# RN-131G_Breakout-v13.net
KiCad netlist of a schematic drawn in EAGLE
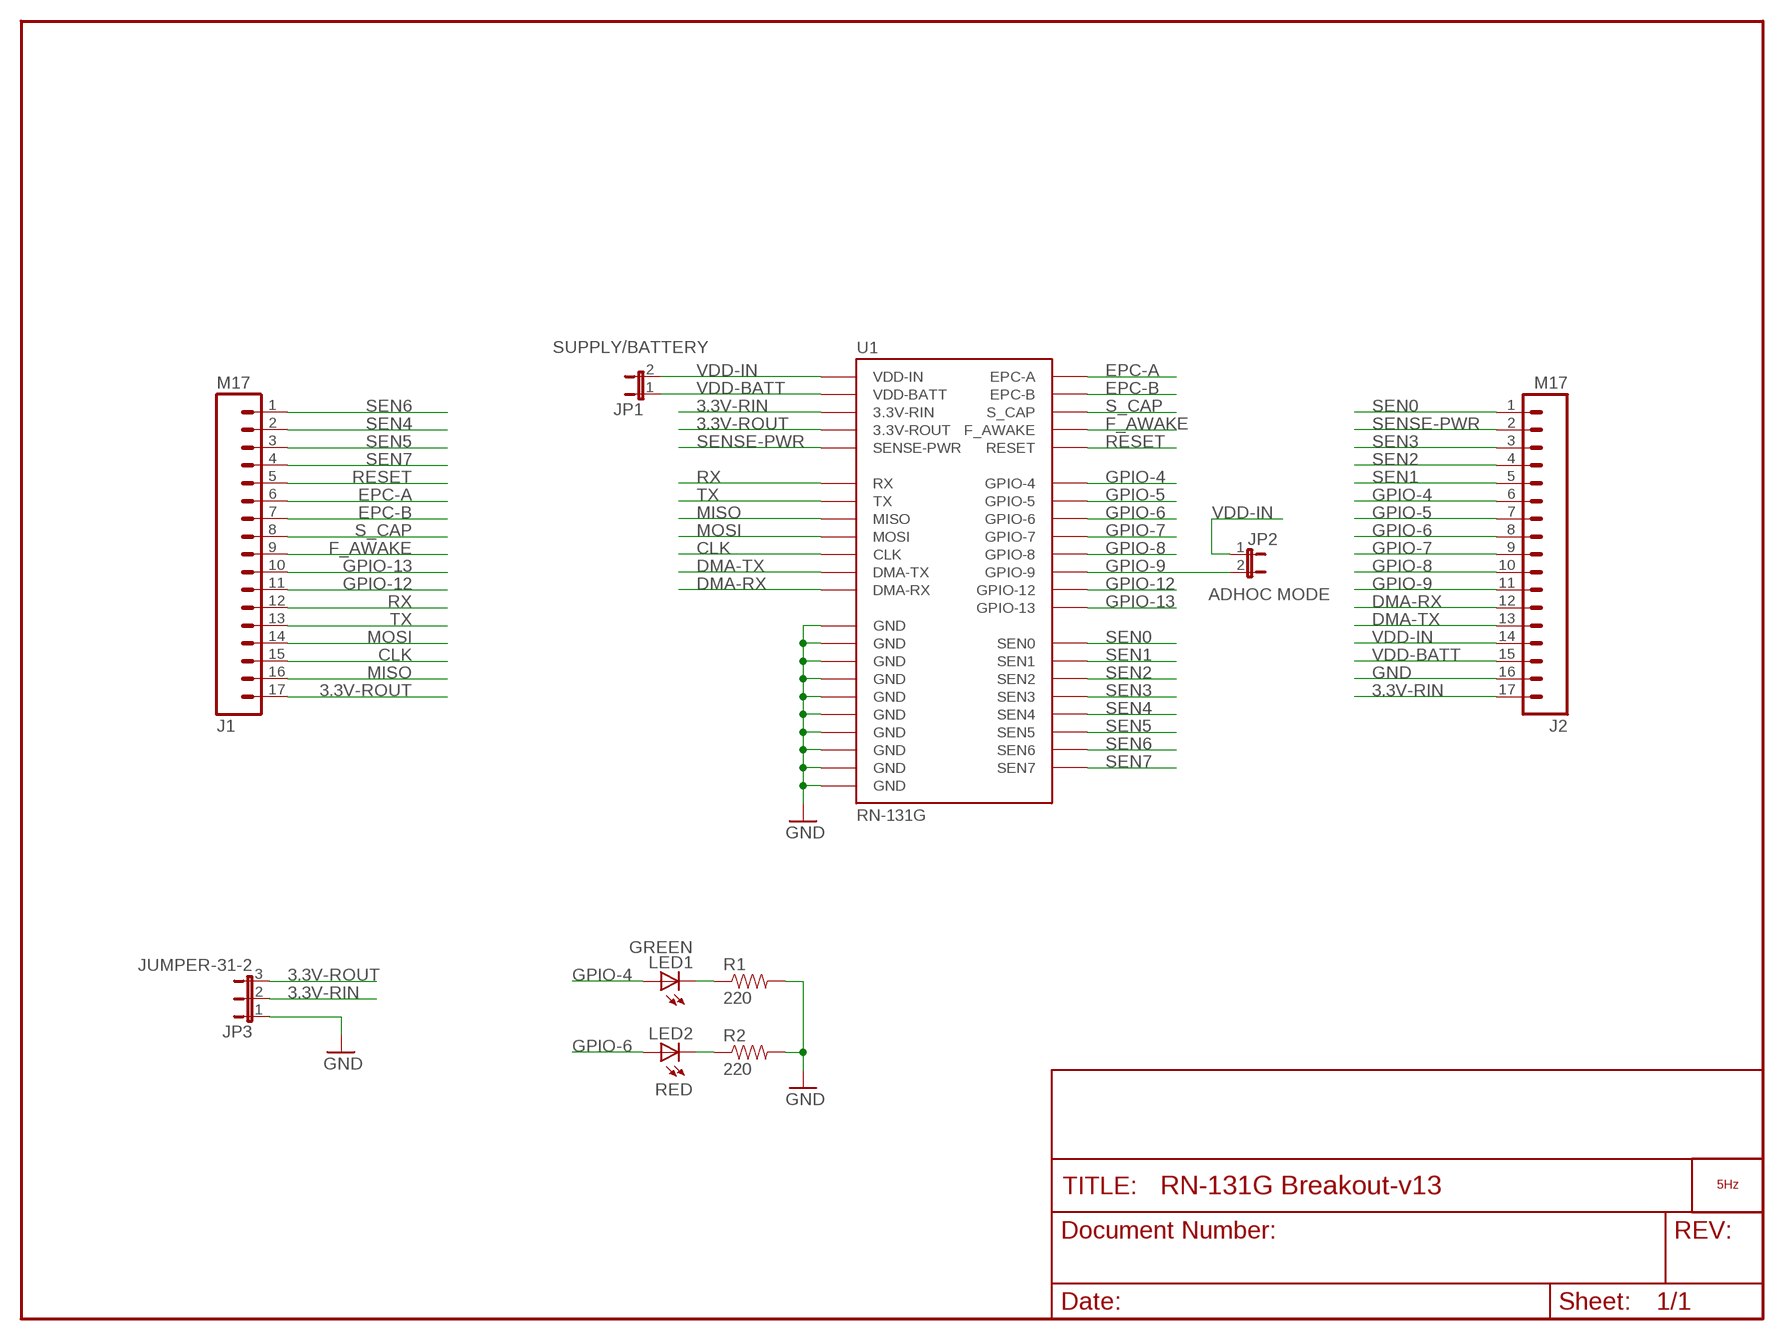
[diagram p0: schematic, sheet 1]

(export (version "E")
  (design (tool "Eeschema 10.0.6"))
  (components
    (comp (ref "J1")
      (value "M17")
      (footprint "eagle-import:1X17")
      (libsource (lib "eagle-import") (part "M17"))
    )
    (comp (ref "J2")
      (value "M17")
      (footprint "eagle-import:1X17")
      (libsource (lib "eagle-import") (part "M17"))
    )
    (comp (ref "JP1")
      (value "JUMPER-2SMD-NO")
      (footprint "eagle-import:SJ_2S-NO")
      (libsource (lib "eagle-import") (part "JUMPER-2SMD-NO"))
    )
    (comp (ref "JP2")
      (value "JUMPER-2SMD-NO")
      (footprint "eagle-import:SJ_2S-NO")
      (libsource (lib "eagle-import") (part "JUMPER-2SMD-NO"))
    )
    (comp (ref "JP3")
      (value "JUMPER-31-2")
      (footprint "eagle-import:SJ_3_PASTE1&2")
      (libsource (lib "eagle-import") (part "JUMPER-31-2"))
    )
    (comp (ref "LED1")
      (value "GREEN")
      (footprint "eagle-import:LED-0603")
      (libsource (lib "eagle-import") (part "LED0603"))
    )
    (comp (ref "LED2")
      (value "RED")
      (footprint "eagle-import:LED-0603")
      (libsource (lib "eagle-import") (part "LED0603"))
    )
    (comp (ref "LOGO1")
      (value "LOGO_5HZ_H_10MM")
      (footprint "eagle-import:5HZ_LOGO_H_10MM")
      (libsource (lib "eagle-import") (part "LOGO_5HZ_H_10MM"))
    )
    (comp (ref "R1")
      (value "220")
      (footprint "eagle-import:0402-RES")
      (libsource (lib "eagle-import") (part "RESISTOR0402-RES"))
    )
    (comp (ref "R2")
      (value "220")
      (footprint "eagle-import:0402-RES")
      (libsource (lib "eagle-import") (part "RESISTOR0402-RES"))
    )
    (comp (ref "U1")
      (value "RN-131G")
      (footprint "eagle-import:RN-131G")
      (libsource (lib "eagle-import") (part "RN-131G"))
    )
  )
  (nets
    (net (code "1") (name "/3.3V-RIN") (class "Default")
      (node (ref "J2") (pin "17") (pinfunction "17_17") (pintype "passive"))
      (node (ref "JP3") (pin "2") (pinfunction "2_2") (pintype "passive"))
      (node (ref "U1") (pin "P$18") (pinfunction "3.3V-RIN_P$18") (pintype "bidirectional"))
    )
    (net (code "2") (name "/3.3V-ROUT") (class "Default")
      (node (ref "J1") (pin "17") (pinfunction "17_17") (pintype "passive"))
      (node (ref "JP3") (pin "3") (pinfunction "3_3") (pintype "passive"))
      (node (ref "U1") (pin "P$17") (pinfunction "3.3V-ROUT_P$17") (pintype "bidirectional"))
    )
    (net (code "3") (name "/CLK") (class "Default")
      (node (ref "J1") (pin "15") (pinfunction "15_15") (pintype "passive"))
      (node (ref "U1") (pin "P$15") (pinfunction "CLK_P$15") (pintype "bidirectional"))
    )
    (net (code "4") (name "/DMA-RX") (class "Default")
      (node (ref "J2") (pin "12") (pinfunction "12_12") (pintype "passive"))
      (node (ref "U1") (pin "P$23") (pinfunction "DMA-RX_P$23") (pintype "bidirectional"))
    )
    (net (code "5") (name "/DMA-TX") (class "Default")
      (node (ref "J2") (pin "13") (pinfunction "13_13") (pintype "passive"))
      (node (ref "U1") (pin "P$22") (pinfunction "DMA-TX_P$22") (pintype "bidirectional"))
    )
    (net (code "6") (name "/EPC-A") (class "Default")
      (node (ref "J1") (pin "6") (pinfunction "6_6") (pintype "passive"))
      (node (ref "U1") (pin "P$6") (pinfunction "EPC-A_P$6") (pintype "bidirectional"))
    )
    (net (code "7") (name "/EPC-B") (class "Default")
      (node (ref "J1") (pin "7") (pinfunction "7_7") (pintype "passive"))
      (node (ref "U1") (pin "P$7") (pinfunction "EPC-B_P$7") (pintype "bidirectional"))
    )
    (net (code "8") (name "/F_AWAKE") (class "Default")
      (node (ref "J1") (pin "9") (pinfunction "9_9") (pintype "passive"))
      (node (ref "U1") (pin "P$9") (pinfunction "F_AWAKE_P$9") (pintype "bidirectional"))
    )
    (net (code "9") (name "/GPIO-4") (class "Default")
      (node (ref "J2") (pin "6") (pinfunction "6_6") (pintype "passive"))
      (node (ref "LED1") (pin "A") (pinfunction "A_A") (pintype "passive"))
      (node (ref "U1") (pin "P$29") (pinfunction "GPIO-4_P$29") (pintype "bidirectional"))
    )
    (net (code "10") (name "/GPIO-5") (class "Default")
      (node (ref "J2") (pin "7") (pinfunction "7_7") (pintype "passive"))
      (node (ref "U1") (pin "P$28") (pinfunction "GPIO-5_P$28") (pintype "bidirectional"))
    )
    (net (code "11") (name "/GPIO-6") (class "Default")
      (node (ref "J2") (pin "8") (pinfunction "8_8") (pintype "passive"))
      (node (ref "LED2") (pin "A") (pinfunction "A_A") (pintype "passive"))
      (node (ref "U1") (pin "P$27") (pinfunction "GPIO-6_P$27") (pintype "bidirectional"))
    )
    (net (code "12") (name "/GPIO-7") (class "Default")
      (node (ref "J2") (pin "9") (pinfunction "9_9") (pintype "passive"))
      (node (ref "U1") (pin "P$26") (pinfunction "GPIO-7_P$26") (pintype "bidirectional"))
    )
    (net (code "13") (name "/GPIO-8") (class "Default")
      (node (ref "J2") (pin "10") (pinfunction "10_10") (pintype "passive"))
      (node (ref "U1") (pin "P$25") (pinfunction "GPIO-8_P$25") (pintype "bidirectional"))
    )
    (net (code "14") (name "/GPIO-9") (class "Default")
      (node (ref "J2") (pin "11") (pinfunction "11_11") (pintype "passive"))
      (node (ref "JP2") (pin "2") (pinfunction "2_2") (pintype "passive"))
      (node (ref "U1") (pin "P$24") (pinfunction "GPIO-9_P$24") (pintype "bidirectional"))
    )
    (net (code "15") (name "/GPIO-12") (class "Default")
      (node (ref "J1") (pin "11") (pinfunction "11_11") (pintype "passive"))
      (node (ref "U1") (pin "P$11") (pinfunction "GPIO-12_P$11") (pintype "bidirectional"))
    )
    (net (code "16") (name "/GPIO-13") (class "Default")
      (node (ref "J1") (pin "10") (pinfunction "10_10") (pintype "passive"))
      (node (ref "U1") (pin "P$10") (pinfunction "GPIO-13_P$10") (pintype "bidirectional"))
    )
    (net (code "17") (name "/MISO") (class "Default")
      (node (ref "J1") (pin "16") (pinfunction "16_16") (pintype "passive"))
      (node (ref "U1") (pin "P$16") (pinfunction "MISO_P$16") (pintype "bidirectional"))
    )
    (net (code "18") (name "/MOSI") (class "Default")
      (node (ref "J1") (pin "14") (pinfunction "14_14") (pintype "passive"))
      (node (ref "U1") (pin "P$14") (pinfunction "MOSI_P$14") (pintype "bidirectional"))
    )
    (net (code "19") (name "/RESET") (class "Default")
      (node (ref "J1") (pin "5") (pinfunction "5_5") (pintype "passive"))
      (node (ref "U1") (pin "P$5") (pinfunction "RESET_P$5") (pintype "bidirectional"))
    )
    (net (code "20") (name "/RX") (class "Default")
      (node (ref "J1") (pin "12") (pinfunction "12_12") (pintype "passive"))
      (node (ref "U1") (pin "P$12") (pinfunction "RX_P$12") (pintype "bidirectional"))
    )
    (net (code "21") (name "/SEN0") (class "Default")
      (node (ref "J2") (pin "1") (pinfunction "1_1") (pintype "passive"))
      (node (ref "U1") (pin "P$34") (pinfunction "SEN0_P$34") (pintype "bidirectional"))
    )
    (net (code "22") (name "/SEN1") (class "Default")
      (node (ref "J2") (pin "5") (pinfunction "5_5") (pintype "passive"))
      (node (ref "U1") (pin "P$30") (pinfunction "SEN1_P$30") (pintype "bidirectional"))
    )
    (net (code "23") (name "/SEN2") (class "Default")
      (node (ref "J2") (pin "4") (pinfunction "4_4") (pintype "passive"))
      (node (ref "U1") (pin "P$31") (pinfunction "SEN2_P$31") (pintype "bidirectional"))
    )
    (net (code "24") (name "/SEN3") (class "Default")
      (node (ref "J2") (pin "3") (pinfunction "3_3") (pintype "passive"))
      (node (ref "U1") (pin "P$32") (pinfunction "SEN3_P$32") (pintype "bidirectional"))
    )
    (net (code "25") (name "/SEN4") (class "Default")
      (node (ref "J1") (pin "2") (pinfunction "2_2") (pintype "passive"))
      (node (ref "U1") (pin "P$2") (pinfunction "SEN4_P$2") (pintype "bidirectional"))
    )
    (net (code "26") (name "/SEN5") (class "Default")
      (node (ref "J1") (pin "3") (pinfunction "3_3") (pintype "passive"))
      (node (ref "U1") (pin "P$3") (pinfunction "SEN5_P$3") (pintype "bidirectional"))
    )
    (net (code "27") (name "/SEN6") (class "Default")
      (node (ref "J1") (pin "1") (pinfunction "1_1") (pintype "passive"))
      (node (ref "U1") (pin "P$1") (pinfunction "SEN6_P$1") (pintype "bidirectional"))
    )
    (net (code "28") (name "/SEN7") (class "Default")
      (node (ref "J1") (pin "4") (pinfunction "4_4") (pintype "passive"))
      (node (ref "U1") (pin "P$4") (pinfunction "SEN7_P$4") (pintype "bidirectional"))
    )
    (net (code "29") (name "/SENSE-PWR") (class "Default")
      (node (ref "J2") (pin "2") (pinfunction "2_2") (pintype "passive"))
      (node (ref "U1") (pin "P$33") (pinfunction "SENSE-PWR_P$33") (pintype "bidirectional"))
    )
    (net (code "30") (name "/S_CAP") (class "Default")
      (node (ref "J1") (pin "8") (pinfunction "8_8") (pintype "passive"))
      (node (ref "U1") (pin "P$8") (pinfunction "S_CAP_P$8") (pintype "bidirectional"))
    )
    (net (code "31") (name "/TX") (class "Default")
      (node (ref "J1") (pin "13") (pinfunction "13_13") (pintype "passive"))
      (node (ref "U1") (pin "P$13") (pinfunction "TX_P$13") (pintype "bidirectional"))
    )
    (net (code "32") (name "/VDD-BATT") (class "Default")
      (node (ref "J2") (pin "15") (pinfunction "15_15") (pintype "passive"))
      (node (ref "JP1") (pin "1") (pinfunction "1_1") (pintype "passive"))
      (node (ref "U1") (pin "P$20") (pinfunction "VDD-BATT_P$20") (pintype "bidirectional"))
    )
    (net (code "33") (name "/VDD-IN") (class "Default")
      (node (ref "J2") (pin "14") (pinfunction "14_14") (pintype "passive"))
      (node (ref "JP1") (pin "2") (pinfunction "2_2") (pintype "passive"))
      (node (ref "JP2") (pin "1") (pinfunction "1_1") (pintype "passive"))
      (node (ref "U1") (pin "P$21") (pinfunction "VDD-IN_P$21") (pintype "bidirectional"))
    )
    (net (code "34") (name "GND") (class "Default")
      (node (ref "J2") (pin "16") (pinfunction "16_16") (pintype "passive"))
      (node (ref "JP3") (pin "1") (pinfunction "1_1") (pintype "passive"))
      (node (ref "R1") (pin "2") (pinfunction "2_2") (pintype "passive"))
      (node (ref "R2") (pin "2") (pinfunction "2_2") (pintype "passive"))
      (node (ref "U1") (pin "P$19") (pinfunction "GND_P$19") (pintype "bidirectional"))
      (node (ref "U1") (pin "P$36") (pinfunction "GND_P$36") (pintype "bidirectional"))
      (node (ref "U1") (pin "P$37") (pinfunction "GND_P$37") (pintype "bidirectional"))
      (node (ref "U1") (pin "P$38") (pinfunction "GND_P$38") (pintype "bidirectional"))
      (node (ref "U1") (pin "P$39") (pinfunction "GND_P$39") (pintype "bidirectional"))
      (node (ref "U1") (pin "P$40") (pinfunction "GND_P$40") (pintype "bidirectional"))
      (node (ref "U1") (pin "P$41") (pinfunction "GND_P$41") (pintype "bidirectional"))
      (node (ref "U1") (pin "P$42") (pinfunction "GND_P$42") (pintype "bidirectional"))
      (node (ref "U1") (pin "P$43") (pinfunction "GND_P$43") (pintype "bidirectional"))
      (node (ref "U1") (pin "P$44") (pinfunction "GND_P$44") (pintype "bidirectional"))
    )
    (net (code "35") (name "Net-(LED1-PadC)") (class "Default")
      (node (ref "LED1") (pin "C") (pinfunction "C_C") (pintype "passive"))
      (node (ref "R1") (pin "1") (pinfunction "1_1") (pintype "passive"))
    )
    (net (code "36") (name "Net-(LED2-PadC)") (class "Default")
      (node (ref "LED2") (pin "C") (pinfunction "C_C") (pintype "passive"))
      (node (ref "R2") (pin "1") (pinfunction "1_1") (pintype "passive"))
    )
  )
)
